# Word_Clock.net
KiCad netlist of a schematic drawn in EAGLE
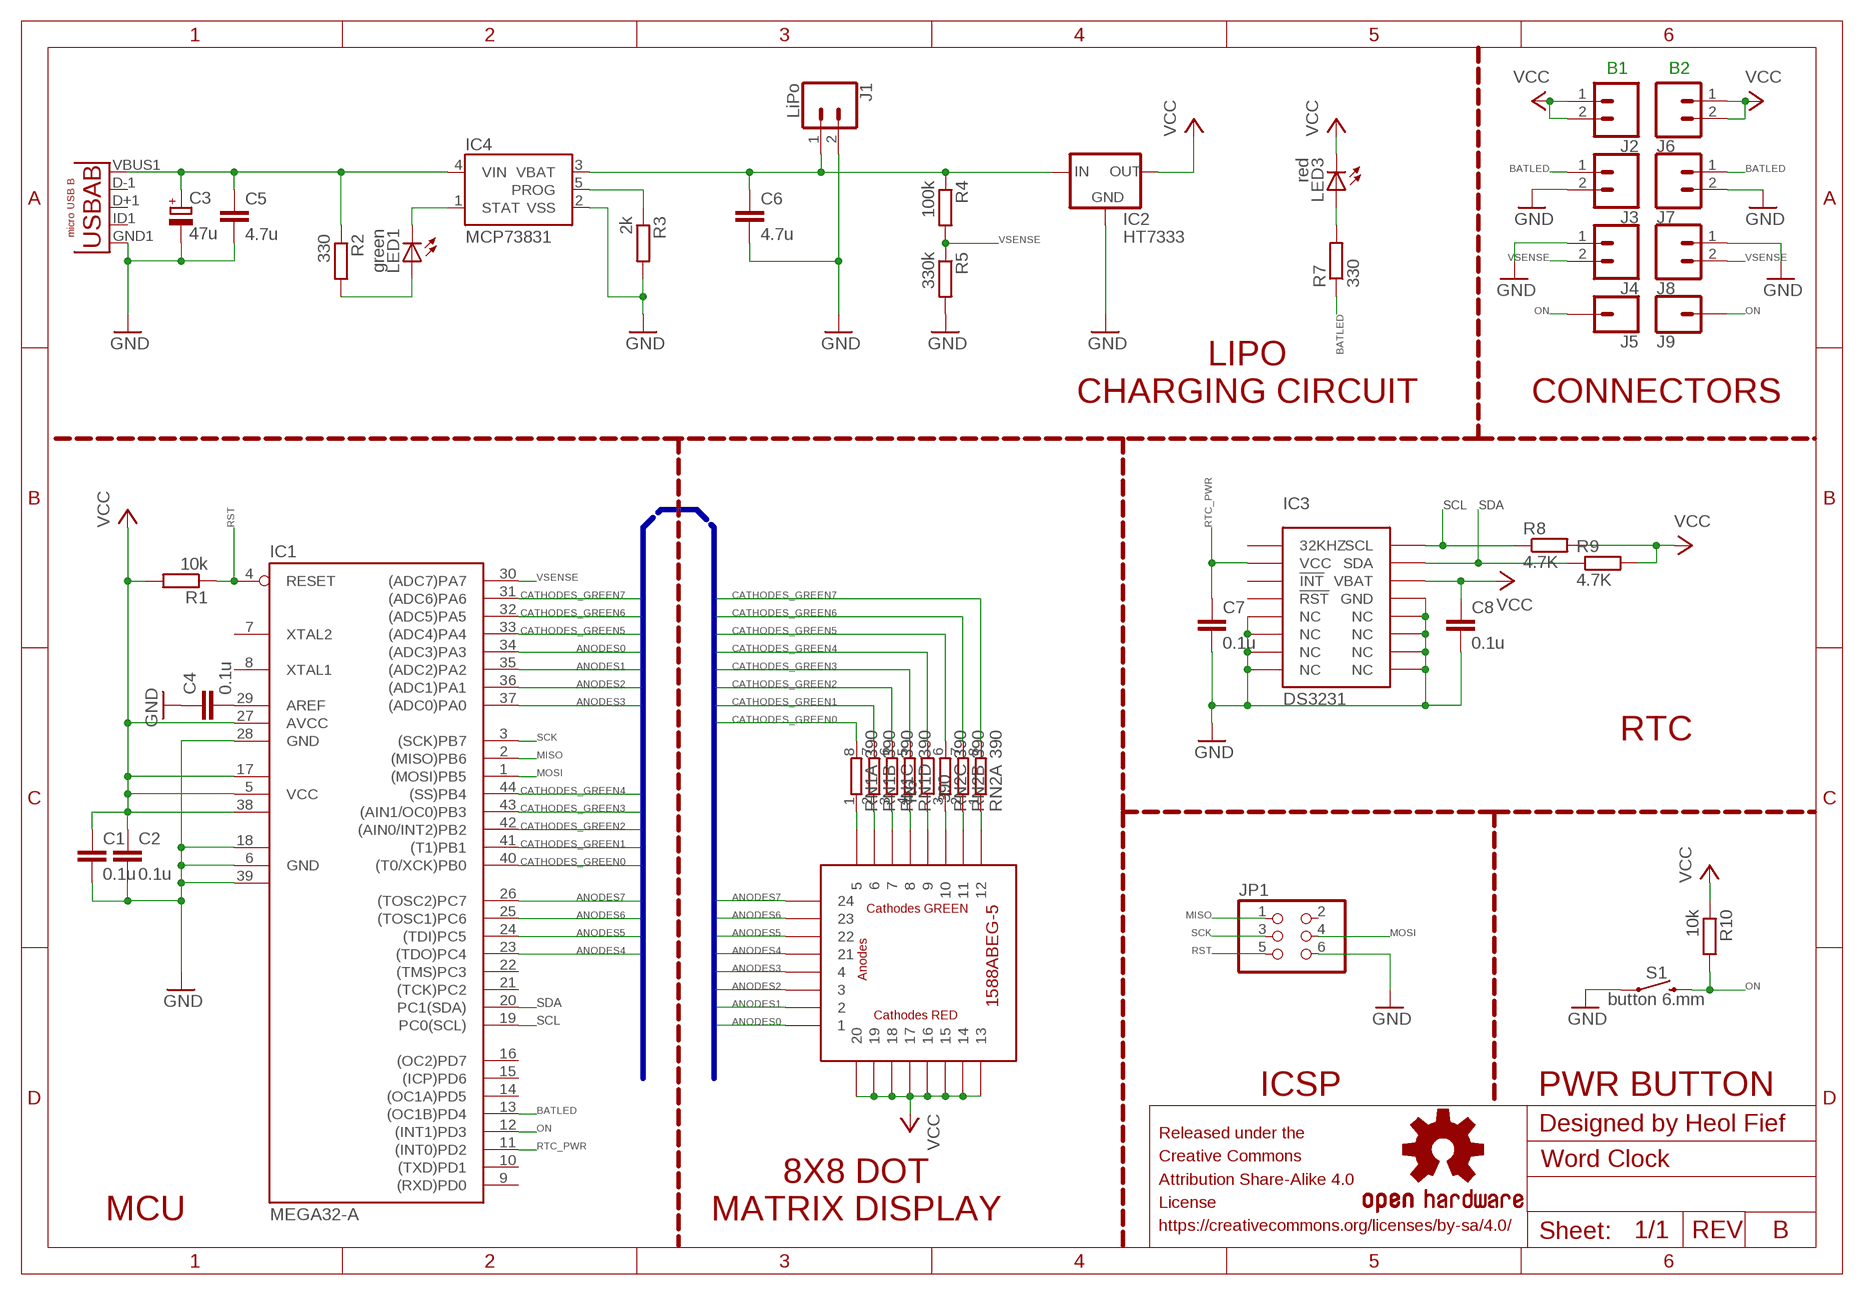
[diagram p0: schematic, sheet 1]

(export (version "E")
  (design (tool "Eeschema 10.0.6"))
  (components
    (comp (ref "C1")
      (value "0.1u")
      (footprint "eagle-import:C0805")
      (libsource (lib "eagle-import") (part "C-EUC0805"))
    )
    (comp (ref "C2")
      (value "0.1u")
      (footprint "eagle-import:C0805")
      (libsource (lib "eagle-import") (part "C-EUC0805"))
    )
    (comp (ref "C3")
      (value "47u")
      (footprint "eagle-import:D_7343-31W")
      (libsource (lib "eagle-import") (part "CPOL-EUD/7343-31W"))
    )
    (comp (ref "C4")
      (value "0.1u")
      (footprint "eagle-import:C0805")
      (libsource (lib "eagle-import") (part "C-EUC0805"))
    )
    (comp (ref "C5")
      (value "4.7u")
      (footprint "eagle-import:C0805")
      (libsource (lib "eagle-import") (part "C-EUC0805"))
    )
    (comp (ref "C6")
      (value "4.7u")
      (footprint "eagle-import:C0805")
      (libsource (lib "eagle-import") (part "C-EUC0805"))
    )
    (comp (ref "C7")
      (value "0.1u")
      (footprint "eagle-import:C0805")
      (libsource (lib "eagle-import") (part "C-EUC0805"))
    )
    (comp (ref "C8")
      (value "0.1u")
      (footprint "eagle-import:C0805")
      (libsource (lib "eagle-import") (part "C-EUC0805"))
    )
    (comp (ref "IC1")
      (value "MEGA32-A")
      (footprint "eagle-import:TQFP44")
      (fields (field (name "MPN") "ATMEGA32-16AU"))
      (libsource (lib "eagle-import") (part "MEGA32-A"))
    )
    (comp (ref "IC2")
      (value "HT7333")
      (footprint "eagle-import:SOT-89")
      (libsource (lib "eagle-import") (part "HT7333"))
    )
    (comp (ref "IC3")
      (value "DS3231")
      (footprint "eagle-import:SOIC-16W")
      (libsource (lib "eagle-import") (part "DS3231SOIC-16W"))
    )
    (comp (ref "IC4")
      (value "MCP73831")
      (footprint "eagle-import:SOT23-5")
      (libsource (lib "eagle-import") (part "MCP73831"))
    )
    (comp (ref "J1")
      (value "LiPo")
      (footprint "eagle-import:MOLEX-1X2")
      (libsource (lib "eagle-import") (part "CONN_02POLAR"))
    )
    (comp (ref "J2")
      (value "CONN_02")
      (footprint "eagle-import:1X02")
      (libsource (lib "eagle-import") (part "CONN_02"))
    )
    (comp (ref "J3")
      (value "CONN_02")
      (footprint "eagle-import:1X02")
      (libsource (lib "eagle-import") (part "CONN_02"))
    )
    (comp (ref "J4")
      (value "CONN_02")
      (footprint "eagle-import:1X02")
      (libsource (lib "eagle-import") (part "CONN_02"))
    )
    (comp (ref "J5")
      (value "CONN_01")
      (footprint "eagle-import:1X01")
      (libsource (lib "eagle-import") (part "CONN_01"))
    )
    (comp (ref "J6")
      (value "CONN_02")
      (footprint "eagle-import:1X02")
      (libsource (lib "eagle-import") (part "CONN_02"))
    )
    (comp (ref "J7")
      (value "CONN_02")
      (footprint "eagle-import:1X02")
      (libsource (lib "eagle-import") (part "CONN_02"))
    )
    (comp (ref "J8")
      (value "CONN_02")
      (footprint "eagle-import:1X02")
      (libsource (lib "eagle-import") (part "CONN_02"))
    )
    (comp (ref "J9")
      (value "CONN_01")
      (footprint "eagle-import:1X01")
      (libsource (lib "eagle-import") (part "CONN_01"))
    )
    (comp (ref "J10")
      (value "USB\"\"")
      (footprint "eagle-import:USB-MICRO-SMD")
      (libsource (lib "eagle-import") (part "USB{dblquote}{dblquote}"))
    )
    (comp (ref "JP1")
      (value "PINHD-2X3/90")
      (footprint "eagle-import:2X03_90")
      (libsource (lib "eagle-import") (part "PINHD-2X3/90"))
    )
    (comp (ref "LED1")
      (value "green")
      (footprint "eagle-import:CHIPLED_1206")
      (libsource (lib "eagle-import") (part "LEDCHIPLED_1206"))
    )
    (comp (ref "LED2")
      (value "1588ABEG-5_8X8-LED_MATRIX")
      (footprint "eagle-import:1588ABEG-5_8X8-LED_MATRIX")
      (libsource (lib "eagle-import") (part "1588ABEG-5_8X8-LED_MATRIX"))
    )
    (comp (ref "LED3")
      (value "red")
      (footprint "eagle-import:CHIPLED_1206")
      (libsource (lib "eagle-import") (part "LEDCHIPLED_1206"))
    )
    (comp (ref "LOGO1")
      (value "OSHW-LOGOL-COPPER")
      (footprint "eagle-import:OSHW-LOGO-L_COPPER")
      (libsource (lib "eagle-import") (part "OSHW-LOGOL-COPPER"))
    )
    (comp (ref "LOGO2")
      (value "OSHW-LOGOL-COPPER")
      (footprint "eagle-import:OSHW-LOGO-L_COPPER")
      (libsource (lib "eagle-import") (part "OSHW-LOGOL-COPPER"))
    )
    (comp (ref "R1")
      (value "10k")
      (footprint "eagle-import:M0805")
      (libsource (lib "eagle-import") (part "R-EU_M0805"))
    )
    (comp (ref "R2")
      (value "330")
      (footprint "eagle-import:M0805")
      (libsource (lib "eagle-import") (part "R-EU_M0805"))
    )
    (comp (ref "R3")
      (value "2k")
      (footprint "eagle-import:M0805")
      (libsource (lib "eagle-import") (part "R-EU_M0805"))
    )
    (comp (ref "R4")
      (value "100k")
      (footprint "eagle-import:M0805")
      (libsource (lib "eagle-import") (part "R-EU_M0805"))
    )
    (comp (ref "R5")
      (value "330k")
      (footprint "eagle-import:M0805")
      (libsource (lib "eagle-import") (part "R-EU_M0805"))
    )
    (comp (ref "R6")
      (value "390")
      (footprint "eagle-import:R0805")
      (libsource (lib "eagle-import") (part "resistor_R-EU_R0805"))
    )
    (comp (ref "R7")
      (value "330")
      (footprint "eagle-import:M0805")
      (libsource (lib "eagle-import") (part "R-EU_M0805"))
    )
    (comp (ref "R8")
      (value "4.7K")
      (footprint "eagle-import:M0805")
      (libsource (lib "eagle-import") (part "R-EU_M0805"))
    )
    (comp (ref "R9")
      (value "4.7K")
      (footprint "eagle-import:M0805")
      (libsource (lib "eagle-import") (part "R-EU_M0805"))
    )
    (comp (ref "R10")
      (value "10k")
      (footprint "eagle-import:M0805")
      (libsource (lib "eagle-import") (part "R-EU_M0805"))
    )
    (comp (ref "RN1")
      (value "390")
      (footprint "eagle-import:0603-ARC")
      (libsource (lib "eagle-import") (part "4R-N0603-ARC"))
    )
    (comp (ref "RN2")
      (value "390")
      (footprint "eagle-import:0603-ARC")
      (libsource (lib "eagle-import") (part "4R-N0603-ARC"))
    )
    (comp (ref "S1")
      (value "button 6.mm")
      (footprint "eagle-import:TACTILE_SWITCH_PTH_6.0MM")
      (libsource (lib "eagle-import") (part "MOMENTARY-SWITCH-SPST-PTH-6.0MM"))
    )
  )
  (nets
    (net (code "1") (name "/ANODES0") (class "Default")
      (node (ref "IC1") (pin "34") (pinfunction "(ADC3)PA3_34") (pintype "bidirectional"))
      (node (ref "LED2") (pin "P$1") (pinfunction "1_P$1") (pintype "bidirectional"))
    )
    (net (code "2") (name "/ANODES1") (class "Default")
      (node (ref "IC1") (pin "35") (pinfunction "(ADC2)PA2_35") (pintype "bidirectional"))
      (node (ref "LED2") (pin "P$2") (pinfunction "2_P$2") (pintype "bidirectional"))
    )
    (net (code "3") (name "/ANODES2") (class "Default")
      (node (ref "IC1") (pin "36") (pinfunction "(ADC1)PA1_36") (pintype "bidirectional"))
      (node (ref "LED2") (pin "P$3") (pinfunction "3_P$3") (pintype "bidirectional"))
    )
    (net (code "4") (name "/ANODES3") (class "Default")
      (node (ref "IC1") (pin "37") (pinfunction "(ADC0)PA0_37") (pintype "bidirectional"))
      (node (ref "LED2") (pin "P$4") (pinfunction "4_P$4") (pintype "bidirectional"))
    )
    (net (code "5") (name "/ANODES4") (class "Default")
      (node (ref "IC1") (pin "23") (pinfunction "(TDO)PC4_23") (pintype "bidirectional"))
      (node (ref "LED2") (pin "P$21") (pinfunction "21_P$21") (pintype "bidirectional"))
    )
    (net (code "6") (name "/ANODES5") (class "Default")
      (node (ref "IC1") (pin "24") (pinfunction "(TDI)PC5_24") (pintype "bidirectional"))
      (node (ref "LED2") (pin "P$22") (pinfunction "22_P$22") (pintype "bidirectional"))
    )
    (net (code "7") (name "/ANODES6") (class "Default")
      (node (ref "IC1") (pin "25") (pinfunction "(TOSC1)PC6_25") (pintype "bidirectional"))
      (node (ref "LED2") (pin "P$23") (pinfunction "23_P$23") (pintype "bidirectional"))
    )
    (net (code "8") (name "/ANODES7") (class "Default")
      (node (ref "IC1") (pin "26") (pinfunction "(TOSC2)PC7_26") (pintype "bidirectional"))
      (node (ref "LED2") (pin "P$24") (pinfunction "24_P$24") (pintype "bidirectional"))
    )
    (net (code "9") (name "/BATLED") (class "Default")
      (node (ref "IC1") (pin "13") (pinfunction "(OC1B)PD4_13") (pintype "bidirectional"))
      (node (ref "J3") (pin "1") (pinfunction "1_1") (pintype "passive"))
      (node (ref "J7") (pin "1") (pinfunction "1_1") (pintype "passive"))
      (node (ref "R7") (pin "1") (pinfunction "1_1") (pintype "passive"))
    )
    (net (code "10") (name "/CATHODES_GREEN0") (class "Default")
      (node (ref "IC1") (pin "40") (pinfunction "(T0/XCK)PB0_40") (pintype "bidirectional"))
      (node (ref "RN1") (pin "8") (pinfunction "2_8") (pintype "passive"))
    )
    (net (code "11") (name "/CATHODES_GREEN1") (class "Default")
      (node (ref "IC1") (pin "41") (pinfunction "(T1)PB1_41") (pintype "bidirectional"))
      (node (ref "RN1") (pin "7") (pinfunction "2_7") (pintype "passive"))
    )
    (net (code "12") (name "/CATHODES_GREEN2") (class "Default")
      (node (ref "IC1") (pin "42") (pinfunction "(AIN0/INT2)PB2_42") (pintype "bidirectional"))
      (node (ref "RN1") (pin "6") (pinfunction "2_6") (pintype "passive"))
    )
    (net (code "13") (name "/CATHODES_GREEN3") (class "Default")
      (node (ref "IC1") (pin "43") (pinfunction "(AIN1/OC0)PB3_43") (pintype "bidirectional"))
      (node (ref "RN1") (pin "5") (pinfunction "2_5") (pintype "passive"))
    )
    (net (code "14") (name "/CATHODES_GREEN4") (class "Default")
      (node (ref "IC1") (pin "44") (pinfunction "(SS)PB4_44") (pintype "bidirectional"))
      (node (ref "R6") (pin "2") (pinfunction "2_2") (pintype "passive"))
    )
    (net (code "15") (name "/CATHODES_GREEN5") (class "Default")
      (node (ref "IC1") (pin "33") (pinfunction "(ADC4)PA4_33") (pintype "bidirectional"))
      (node (ref "RN2") (pin "6") (pinfunction "2_6") (pintype "passive"))
    )
    (net (code "16") (name "/CATHODES_GREEN6") (class "Default")
      (node (ref "IC1") (pin "32") (pinfunction "(ADC5)PA5_32") (pintype "bidirectional"))
      (node (ref "RN2") (pin "7") (pinfunction "2_7") (pintype "passive"))
    )
    (net (code "17") (name "/CATHODES_GREEN7") (class "Default")
      (node (ref "IC1") (pin "31") (pinfunction "(ADC6)PA6_31") (pintype "bidirectional"))
      (node (ref "RN2") (pin "8") (pinfunction "2_8") (pintype "passive"))
    )
    (net (code "18") (name "/MISO") (class "Default")
      (node (ref "IC1") (pin "2") (pinfunction "(MISO)PB6_2") (pintype "bidirectional"))
      (node (ref "JP1") (pin "1") (pinfunction "1_1") (pintype "passive"))
    )
    (net (code "19") (name "/MOSI") (class "Default")
      (node (ref "IC1") (pin "1") (pinfunction "(MOSI)PB5_1") (pintype "bidirectional"))
      (node (ref "JP1") (pin "4") (pinfunction "4_4") (pintype "passive"))
    )
    (net (code "20") (name "/ON") (class "Default")
      (node (ref "IC1") (pin "12") (pinfunction "(INT1)PD3_12") (pintype "bidirectional"))
      (node (ref "J5") (pin "1") (pinfunction "1_1") (pintype "passive"))
      (node (ref "J9") (pin "1") (pinfunction "1_1") (pintype "passive"))
      (node (ref "R10") (pin "2") (pinfunction "2_2") (pintype "passive"))
      (node (ref "S1") (pin "3") (pinfunction "2_3") (pintype "passive"))
      (node (ref "S1") (pin "4") (pinfunction "2_4") (pintype "passive"))
    )
    (net (code "21") (name "/RST") (class "Default")
      (node (ref "IC1") (pin "4") (pinfunction "RESET_4") (pintype "input"))
      (node (ref "JP1") (pin "5") (pinfunction "5_5") (pintype "passive"))
      (node (ref "R1") (pin "1") (pinfunction "1_1") (pintype "passive"))
    )
    (net (code "22") (name "/RTC_PWR") (class "Default")
      (node (ref "C7") (pin "1") (pinfunction "1_1") (pintype "passive"))
      (node (ref "IC1") (pin "11") (pinfunction "(INT0)PD2_11") (pintype "bidirectional"))
      (node (ref "IC3") (pin "2") (pinfunction "VCC_2") (pintype "bidirectional"))
    )
    (net (code "23") (name "/SCK") (class "Default")
      (node (ref "IC1") (pin "3") (pinfunction "(SCK)PB7_3") (pintype "bidirectional"))
      (node (ref "JP1") (pin "3") (pinfunction "3_3") (pintype "passive"))
    )
    (net (code "24") (name "/SCL") (class "Default")
      (node (ref "IC1") (pin "19") (pinfunction "PC0(SCL)_19") (pintype "bidirectional"))
      (node (ref "IC3") (pin "16") (pinfunction "SCL_16") (pintype "bidirectional"))
      (node (ref "R8") (pin "1") (pinfunction "1_1") (pintype "passive"))
    )
    (net (code "25") (name "/SDA") (class "Default")
      (node (ref "IC1") (pin "20") (pinfunction "PC1(SDA)_20") (pintype "bidirectional"))
      (node (ref "IC3") (pin "15") (pinfunction "SDA_15") (pintype "bidirectional"))
      (node (ref "R9") (pin "1") (pinfunction "1_1") (pintype "passive"))
    )
    (net (code "26") (name "/VSENSE") (class "Default")
      (node (ref "IC1") (pin "30") (pinfunction "(ADC7)PA7_30") (pintype "bidirectional"))
      (node (ref "J4") (pin "2") (pinfunction "2_2") (pintype "passive"))
      (node (ref "J8") (pin "2") (pinfunction "2_2") (pintype "passive"))
      (node (ref "R4") (pin "2") (pinfunction "2_2") (pintype "passive"))
      (node (ref "R5") (pin "1") (pinfunction "1_1") (pintype "passive"))
    )
    (net (code "27") (name "GND") (class "Default")
      (node (ref "C1") (pin "2") (pinfunction "2_2") (pintype "passive"))
      (node (ref "C2") (pin "2") (pinfunction "2_2") (pintype "passive"))
      (node (ref "C3") (pin "-") (pinfunction "-_-") (pintype "passive"))
      (node (ref "C4") (pin "1") (pinfunction "1_1") (pintype "passive"))
      (node (ref "C5") (pin "2") (pinfunction "2_2") (pintype "passive"))
      (node (ref "C6") (pin "2") (pinfunction "2_2") (pintype "passive"))
      (node (ref "C7") (pin "2") (pinfunction "2_2") (pintype "passive"))
      (node (ref "C8") (pin "2") (pinfunction "2_2") (pintype "passive"))
      (node (ref "IC1") (pin "18") (pinfunction "GND1_18") (pintype "power_in"))
      (node (ref "IC1") (pin "28") (pinfunction "GND_28") (pintype "power_in"))
      (node (ref "IC1") (pin "39") (pinfunction "GND2_39") (pintype "power_in"))
      (node (ref "IC1") (pin "6") (pinfunction "GND_6") (pintype "power_in"))
      (node (ref "IC2") (pin "2") (pinfunction "GND_2") (pintype "input"))
      (node (ref "IC3") (pin "10") (pinfunction "NC_10") (pintype "bidirectional"))
      (node (ref "IC3") (pin "11") (pinfunction "NC_11") (pintype "bidirectional"))
      (node (ref "IC3") (pin "12") (pinfunction "NC_12") (pintype "bidirectional"))
      (node (ref "IC3") (pin "13") (pinfunction "GND_13") (pintype "bidirectional"))
      (node (ref "IC3") (pin "5") (pinfunction "NC_5") (pintype "bidirectional"))
      (node (ref "IC3") (pin "6") (pinfunction "NC_6") (pintype "bidirectional"))
      (node (ref "IC3") (pin "7") (pinfunction "NC_7") (pintype "bidirectional"))
      (node (ref "IC3") (pin "8") (pinfunction "NC_8") (pintype "bidirectional"))
      (node (ref "IC3") (pin "9") (pinfunction "NC_9") (pintype "bidirectional"))
      (node (ref "IC4") (pin "2") (pinfunction "VSS_2") (pintype "power_in"))
      (node (ref "J1") (pin "2") (pinfunction "2_2") (pintype "passive"))
      (node (ref "J10") (pin "GND1") (pinfunction "GND_GND1") (pintype "bidirectional"))
      (node (ref "J3") (pin "2") (pinfunction "2_2") (pintype "passive"))
      (node (ref "J4") (pin "1") (pinfunction "1_1") (pintype "passive"))
      (node (ref "J7") (pin "2") (pinfunction "2_2") (pintype "passive"))
      (node (ref "J8") (pin "1") (pinfunction "1_1") (pintype "passive"))
      (node (ref "JP1") (pin "6") (pinfunction "6_6") (pintype "passive"))
      (node (ref "R3") (pin "2") (pinfunction "2_2") (pintype "passive"))
      (node (ref "R5") (pin "2") (pinfunction "2_2") (pintype "passive"))
      (node (ref "S1") (pin "1") (pinfunction "1_1") (pintype "passive"))
      (node (ref "S1") (pin "2") (pinfunction "1_2") (pintype "passive"))
    )
    (net (code "28") (name "Net-(IC1-AREF)") (class "Default")
      (node (ref "C4") (pin "2") (pinfunction "2_2") (pintype "passive"))
      (node (ref "IC1") (pin "29") (pinfunction "AREF_29") (pintype "passive"))
    )
    (net (code "29") (name "Net-(IC4-PROG)") (class "Default")
      (node (ref "IC4") (pin "5") (pinfunction "PROG_5") (pintype "input"))
      (node (ref "R3") (pin "1") (pinfunction "1_1") (pintype "passive"))
    )
    (net (code "30") (name "Net-(IC4-STAT)") (class "Default")
      (node (ref "IC4") (pin "1") (pinfunction "STAT_1") (pintype "output"))
      (node (ref "LED1") (pin "C") (pinfunction "C_C") (pintype "passive"))
    )
    (net (code "31") (name "Net-(IC4-VBAT)") (class "Default")
      (node (ref "C6") (pin "1") (pinfunction "1_1") (pintype "passive"))
      (node (ref "IC2") (pin "3") (pinfunction "IN_3") (pintype "input"))
      (node (ref "IC2") (pin "4") (pinfunction "IN_4") (pintype "input"))
      (node (ref "IC4") (pin "3") (pinfunction "VBAT_3") (pintype "power_in"))
      (node (ref "J1") (pin "1") (pinfunction "1_1") (pintype "passive"))
      (node (ref "R4") (pin "1") (pinfunction "1_1") (pintype "passive"))
    )
    (net (code "32") (name "Net-(IC4-VIN)") (class "Default")
      (node (ref "C3") (pin "+") (pinfunction "+_+") (pintype "passive"))
      (node (ref "C5") (pin "1") (pinfunction "1_1") (pintype "passive"))
      (node (ref "IC4") (pin "4") (pinfunction "VIN_4") (pintype "power_in"))
      (node (ref "J10") (pin "VBUS1") (pinfunction "VBUS_VBUS1") (pintype "bidirectional"))
      (node (ref "R2") (pin "1") (pinfunction "1_1") (pintype "passive"))
    )
    (net (code "33") (name "Net-(LED1-PadA)") (class "Default")
      (node (ref "LED1") (pin "A") (pinfunction "A_A") (pintype "passive"))
      (node (ref "R2") (pin "2") (pinfunction "2_2") (pintype "passive"))
    )
    (net (code "34") (name "Net-(LED2-5)") (class "Default")
      (node (ref "LED2") (pin "P$5") (pinfunction "5_P$5") (pintype "bidirectional"))
      (node (ref "RN1") (pin "1") (pinfunction "1_1") (pintype "passive"))
    )
    (net (code "35") (name "Net-(LED2-6)") (class "Default")
      (node (ref "LED2") (pin "P$6") (pinfunction "6_P$6") (pintype "bidirectional"))
      (node (ref "RN1") (pin "2") (pinfunction "1_2") (pintype "passive"))
    )
    (net (code "36") (name "Net-(LED2-7)") (class "Default")
      (node (ref "LED2") (pin "P$7") (pinfunction "7_P$7") (pintype "bidirectional"))
      (node (ref "RN1") (pin "3") (pinfunction "1_3") (pintype "passive"))
    )
    (net (code "37") (name "Net-(LED2-8)") (class "Default")
      (node (ref "LED2") (pin "P$8") (pinfunction "8_P$8") (pintype "bidirectional"))
      (node (ref "RN1") (pin "4") (pinfunction "1_4") (pintype "passive"))
    )
    (net (code "38") (name "Net-(LED2-9)") (class "Default")
      (node (ref "LED2") (pin "P$9") (pinfunction "9_P$9") (pintype "bidirectional"))
      (node (ref "R6") (pin "1") (pinfunction "1_1") (pintype "passive"))
    )
    (net (code "39") (name "Net-(LED2-10)") (class "Default")
      (node (ref "LED2") (pin "P$10") (pinfunction "10_P$10") (pintype "bidirectional"))
      (node (ref "RN2") (pin "3") (pinfunction "1_3") (pintype "passive"))
    )
    (net (code "40") (name "Net-(LED2-11)") (class "Default")
      (node (ref "LED2") (pin "P$11") (pinfunction "11_P$11") (pintype "bidirectional"))
      (node (ref "RN2") (pin "2") (pinfunction "1_2") (pintype "passive"))
    )
    (net (code "41") (name "Net-(LED2-12)") (class "Default")
      (node (ref "LED2") (pin "P$12") (pinfunction "12_P$12") (pintype "bidirectional"))
      (node (ref "RN2") (pin "1") (pinfunction "1_1") (pintype "passive"))
    )
    (net (code "42") (name "Net-(LED3-PadA)") (class "Default")
      (node (ref "LED3") (pin "A") (pinfunction "A_A") (pintype "passive"))
      (node (ref "R7") (pin "2") (pinfunction "2_2") (pintype "passive"))
    )
    (net (code "43") (name "VCC") (class "Default")
      (node (ref "C1") (pin "1") (pinfunction "1_1") (pintype "passive"))
      (node (ref "C2") (pin "1") (pinfunction "1_1") (pintype "passive"))
      (node (ref "C8") (pin "1") (pinfunction "1_1") (pintype "passive"))
      (node (ref "IC1") (pin "17") (pinfunction "VCC1_17") (pintype "power_in"))
      (node (ref "IC1") (pin "27") (pinfunction "AVCC_27") (pintype "power_in"))
      (node (ref "IC1") (pin "38") (pinfunction "VCC2_38") (pintype "power_in"))
      (node (ref "IC1") (pin "5") (pinfunction "VCC_5") (pintype "power_in"))
      (node (ref "IC2") (pin "1") (pinfunction "OUT_1") (pintype "passive"))
      (node (ref "IC3") (pin "14") (pinfunction "VBAT_14") (pintype "bidirectional"))
      (node (ref "J2") (pin "1") (pinfunction "1_1") (pintype "passive"))
      (node (ref "J2") (pin "2") (pinfunction "2_2") (pintype "passive"))
      (node (ref "J6") (pin "1") (pinfunction "1_1") (pintype "passive"))
      (node (ref "J6") (pin "2") (pinfunction "2_2") (pintype "passive"))
      (node (ref "LED2") (pin "P$13") (pinfunction "13_P$13") (pintype "bidirectional"))
      (node (ref "LED2") (pin "P$14") (pinfunction "14_P$14") (pintype "bidirectional"))
      (node (ref "LED2") (pin "P$15") (pinfunction "15_P$15") (pintype "bidirectional"))
      (node (ref "LED2") (pin "P$16") (pinfunction "16_P$16") (pintype "bidirectional"))
      (node (ref "LED2") (pin "P$17") (pinfunction "17_P$17") (pintype "bidirectional"))
      (node (ref "LED2") (pin "P$18") (pinfunction "18_P$18") (pintype "bidirectional"))
      (node (ref "LED2") (pin "P$19") (pinfunction "19_P$19") (pintype "bidirectional"))
      (node (ref "LED2") (pin "P$20") (pinfunction "20_P$20") (pintype "bidirectional"))
      (node (ref "LED3") (pin "C") (pinfunction "C_C") (pintype "passive"))
      (node (ref "R1") (pin "2") (pinfunction "2_2") (pintype "passive"))
      (node (ref "R10") (pin "1") (pinfunction "1_1") (pintype "passive"))
      (node (ref "R8") (pin "2") (pinfunction "2_2") (pintype "passive"))
      (node (ref "R9") (pin "2") (pinfunction "2_2") (pintype "passive"))
    )
    (net (code "44") (name "unconnected-(IC1-(ICP)PD6-Pad15)") (class "Default")
      (node (ref "IC1") (pin "15") (pinfunction "(ICP)PD6_15") (pintype "bidirectional"))
    )
    (net (code "45") (name "unconnected-(IC1-(OC1A)PD5-Pad14)") (class "Default")
      (node (ref "IC1") (pin "14") (pinfunction "(OC1A)PD5_14") (pintype "bidirectional"))
    )
    (net (code "46") (name "unconnected-(IC1-(OC2)PD7-Pad16)") (class "Default")
      (node (ref "IC1") (pin "16") (pinfunction "(OC2)PD7_16") (pintype "bidirectional"))
    )
    (net (code "47") (name "unconnected-(IC1-(RXD)PD0-Pad9)") (class "Default")
      (node (ref "IC1") (pin "9") (pinfunction "(RXD)PD0_9") (pintype "bidirectional"))
    )
    (net (code "48") (name "unconnected-(IC1-(TCK)PC2-Pad21)") (class "Default")
      (node (ref "IC1") (pin "21") (pinfunction "(TCK)PC2_21") (pintype "bidirectional"))
    )
    (net (code "49") (name "unconnected-(IC1-(TMS)PC3-Pad22)") (class "Default")
      (node (ref "IC1") (pin "22") (pinfunction "(TMS)PC3_22") (pintype "bidirectional"))
    )
    (net (code "50") (name "unconnected-(IC1-(TXD)PD1-Pad10)") (class "Default")
      (node (ref "IC1") (pin "10") (pinfunction "(TXD)PD1_10") (pintype "bidirectional"))
    )
    (net (code "51") (name "unconnected-(IC1-XTAL1-Pad8)") (class "Default")
      (node (ref "IC1") (pin "8") (pinfunction "XTAL1_8") (pintype "bidirectional"))
    )
    (net (code "52") (name "unconnected-(IC1-XTAL2-Pad7)") (class "Default")
      (node (ref "IC1") (pin "7") (pinfunction "XTAL2_7") (pintype "bidirectional"))
    )
    (net (code "53") (name "unconnected-(IC3-32KHZ-Pad1)") (class "Default")
      (node (ref "IC3") (pin "1") (pinfunction "32KHZ_1") (pintype "bidirectional"))
    )
    (net (code "54") (name "unconnected-(IC3-~{INT}-Pad3)") (class "Default")
      (node (ref "IC3") (pin "3") (pinfunction "~{INT}_3") (pintype "bidirectional"))
    )
    (net (code "55") (name "unconnected-(IC3-~{RST}-Pad4)") (class "Default")
      (node (ref "IC3") (pin "4") (pinfunction "~{RST}_4") (pintype "bidirectional"))
    )
    (net (code "56") (name "unconnected-(J10-D+-PadD+1)") (class "Default")
      (node (ref "J10") (pin "D+1") (pinfunction "D+_D+1") (pintype "bidirectional"))
    )
    (net (code "57") (name "unconnected-(J10-D--PadD-1)") (class "Default")
      (node (ref "J10") (pin "D-1") (pinfunction "D-_D-1") (pintype "bidirectional"))
    )
    (net (code "58") (name "unconnected-(J10-USBID-PadID1)") (class "Default")
      (node (ref "J10") (pin "ID1") (pinfunction "USBID_ID1") (pintype "bidirectional"))
    )
    (net (code "59") (name "unconnected-(JP1-Pad2)") (class "Default")
      (node (ref "JP1") (pin "2") (pinfunction "2_2") (pintype "passive"))
    )
  )
)
